# SCH_d_02_e_04.net
KiCad netlist of a schematic drawn in EasyEDA
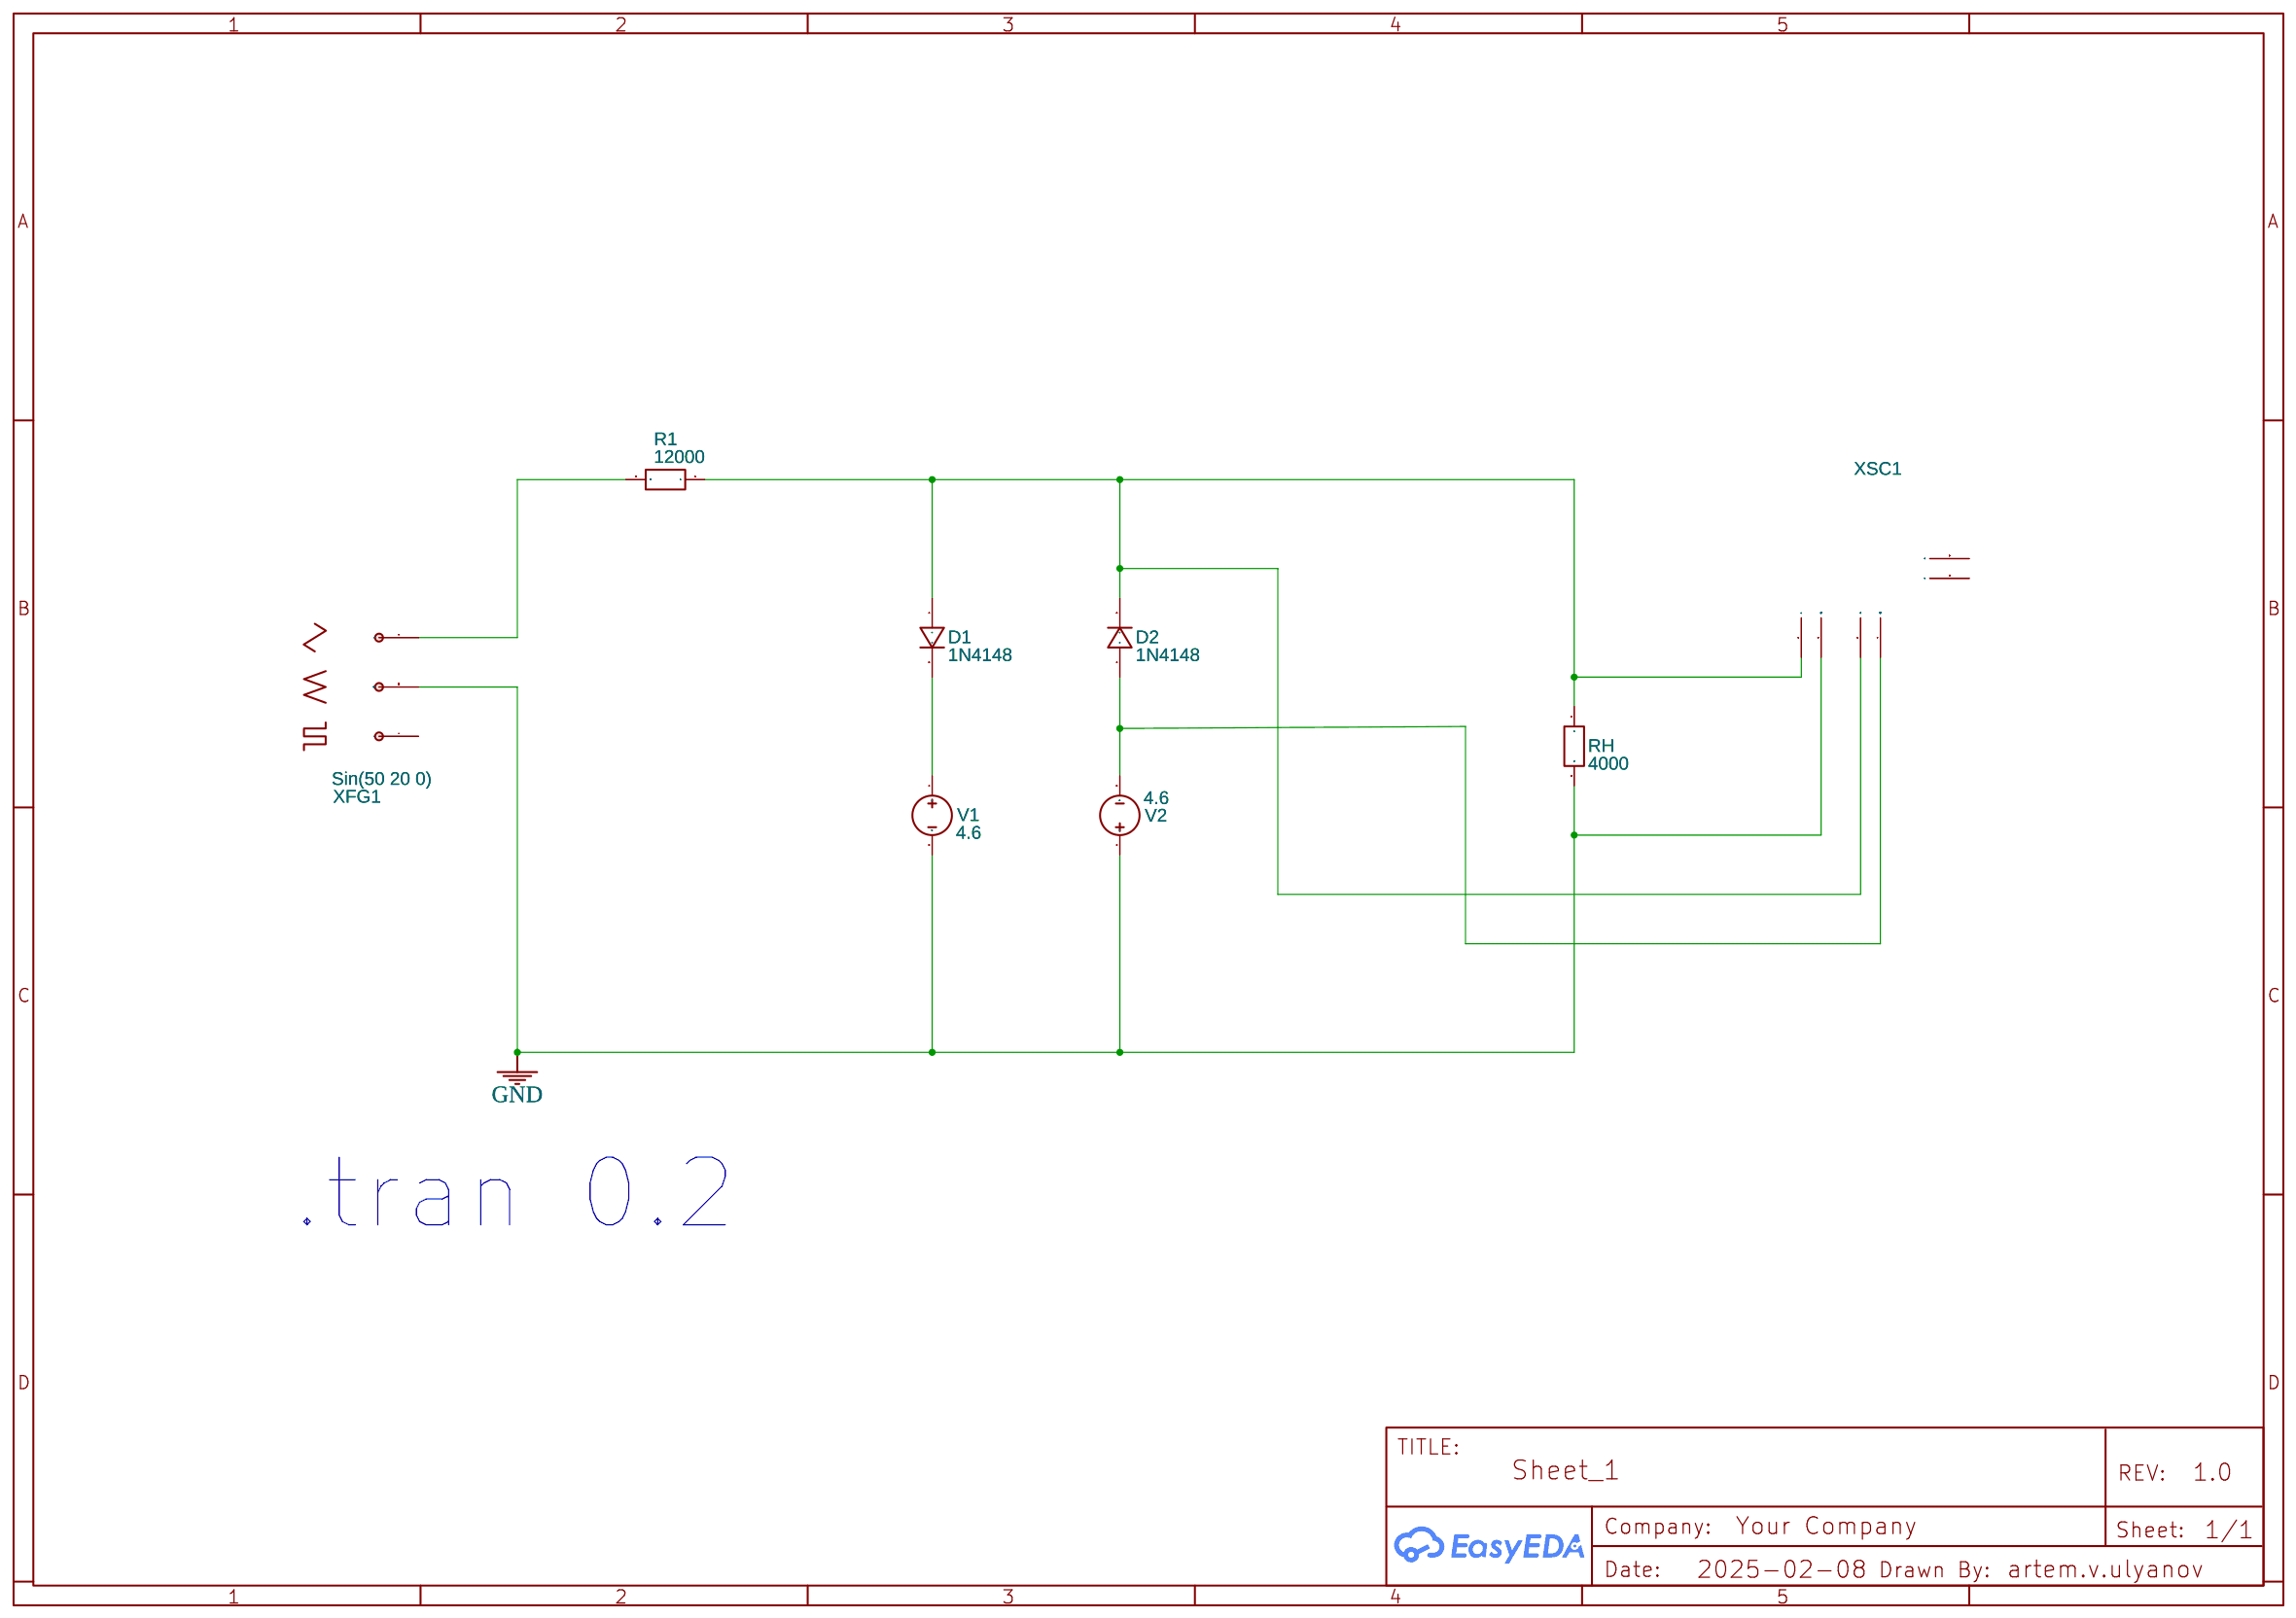
[diagram p0: schematic sheet]

(export (version "E")
  (design (tool "Eeschema 10.0.6"))
  (components
    (comp (ref "D1") (value "1N4148") (libsource (lib "") (part "1N4148")))
    (comp (ref "D2") (value "1N4148") (libsource (lib "") (part "1N4148_1")))
    (comp (ref "R1") (value "12000") (libsource (lib "") (part "R_0603_EU_1")))
    (comp (ref "RH") (value "4000") (libsource (lib "") (part "R_0603_EU")))
    (comp (ref "V1") (value "4.6") (libsource (lib "") (part "VDC")))
    (comp (ref "V2") (value "4.6") (libsource (lib "") (part "VDC_1")))
    (comp (ref "XFG1") (value "Sin(50 20 0)") (libsource (lib "") (part "FUNCTIONGENERATOR")))
    (comp (ref "XSC1") (value "Oscilloscope") (libsource (lib "") (part "OSCILLOSCOPE")))
  )
  (nets
    (net (code "1") (name "GND") (class "Default")
      (node (ref "RH") (pin "2") (pinfunction "2_2") (pintype "unspecified"))
      (node (ref "V1") (pin "2") (pinfunction "2_2") (pintype "unspecified"))
      (node (ref "V2") (pin "1") (pinfunction "1_1") (pintype "unspecified"))
      (node (ref "XFG1") (pin "COM") (pinfunction "COM_COM") (pintype "unspecified"))
      (node (ref "XSC1") (pin "2") (pinfunction "GND1_2") (pintype "unspecified"))
    )
    (net (code "2") (name "Net-(D1-A)") (class "Default")
      (node (ref "D1") (pin "1") (pinfunction "A_1") (pintype "unspecified"))
      (node (ref "D2") (pin "2") (pinfunction "K_2") (pintype "unspecified"))
      (node (ref "R1") (pin "1") (pinfunction "1_1") (pintype "unspecified"))
      (node (ref "RH") (pin "1") (pinfunction "1_1") (pintype "unspecified"))
      (node (ref "XSC1") (pin "1") (pinfunction "A_1") (pintype "unspecified"))
      (node (ref "XSC1") (pin "3") (pinfunction "B_3") (pintype "unspecified"))
    )
    (net (code "3") (name "Net-(D1-K)") (class "Default")
      (node (ref "D1") (pin "2") (pinfunction "K_2") (pintype "unspecified"))
      (node (ref "V1") (pin "1") (pinfunction "1_1") (pintype "unspecified"))
    )
    (net (code "4") (name "Net-(D2-A)") (class "Default")
      (node (ref "D2") (pin "1") (pinfunction "A_1") (pintype "unspecified"))
      (node (ref "V2") (pin "2") (pinfunction "2_2") (pintype "unspecified"))
      (node (ref "XSC1") (pin "4") (pinfunction "GND2_4") (pintype "unspecified"))
    )
    (net (code "5") (name "Net-(R1-Pad2)") (class "Default")
      (node (ref "R1") (pin "2") (pinfunction "2_2") (pintype "unspecified"))
      (node (ref "XFG1") (pin "+") (pinfunction "+_+") (pintype "unspecified"))
    )
    (net (code "6") (name "unconnected-(XFG1-Pad-)") (class "Default")
      (node (ref "XFG1") (pin "-") (pinfunction "-_-") (pintype "unspecified"))
    )
    (net (code "7") (name "unconnected-(XSC1-T+-Pad5)") (class "Default")
      (node (ref "XSC1") (pin "5") (pinfunction "T+_5") (pintype "unspecified"))
    )
    (net (code "8") (name "unconnected-(XSC1-T--Pad6)") (class "Default")
      (node (ref "XSC1") (pin "6") (pinfunction "T-_6") (pintype "unspecified"))
    )
  )
)
